# Power.net
KiCad netlist of a schematic drawn in Altium Designer
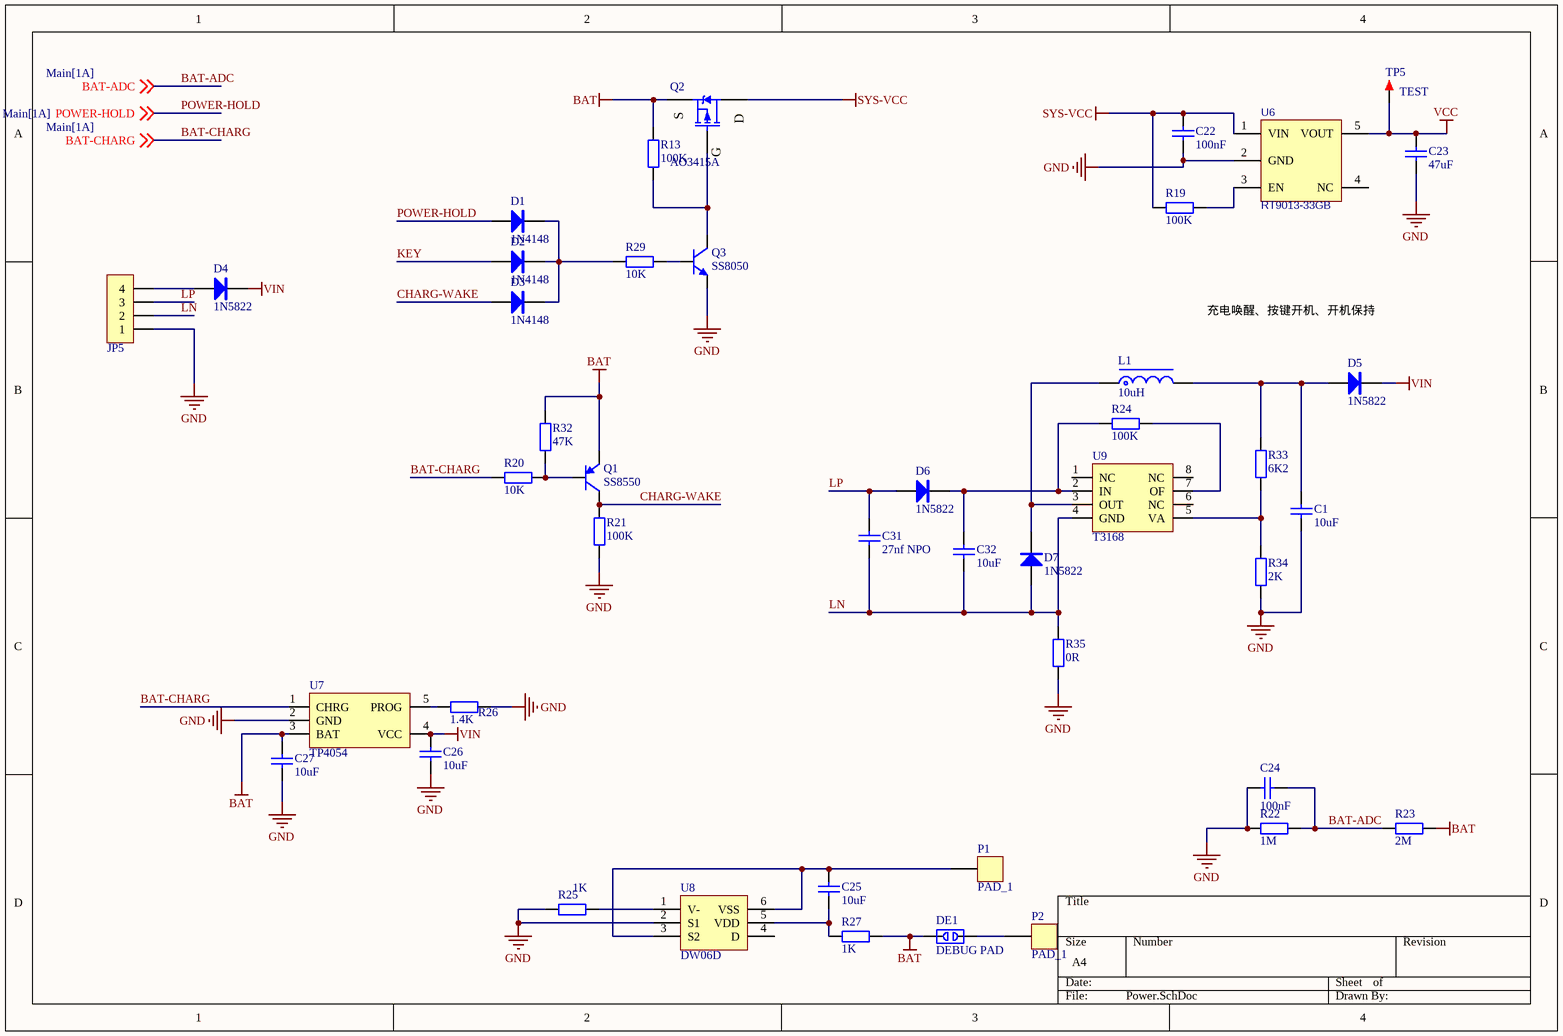
[diagram p0: Power.SchDoc]

(export (version "E")
  (design (tool "Eeschema 10.0.6"))
  (components
    (comp (ref "C1")
      (value "10uF")
      (footprint "C1206_M")
      (description "贴片电容/MLCC电容")
      (libsource (lib "0.1 - 电阻-电容-电感-晶振-晶体-磁珠-电位器-法拉电容-馈通电容") (part "C"))
    )
    (comp (ref "C22")
      (value "100nF")
      (footprint "C0402_M")
      (description "贴片电容/MLCC电容")
      (libsource (lib "0.1 - 电阻-电容-电感-晶振-晶体-磁珠-电位器-法拉电容-馈通电容") (part "C"))
    )
    (comp (ref "C23")
      (value "47uF")
      (footprint "C0603_L")
      (description "贴片电容/MLCC电容")
      (libsource (lib "0.1 - 电阻-电容-电感-晶振-晶体-磁珠-电位器-法拉电容-馈通电容") (part "C"))
    )
    (comp (ref "C24")
      (value "100nF")
      (footprint "C0402_M")
      (description "贴片电容/MLCC电容")
      (libsource (lib "0.1 - 电阻-电容-电感-晶振-晶体-磁珠-电位器-法拉电容-馈通电容") (part "C"))
    )
    (comp (ref "C25")
      (value "10uF")
      (footprint "C0402_M")
      (description "贴片电容/MLCC电容")
      (libsource (lib "0.1 - 电阻-电容-电感-晶振-晶体-磁珠-电位器-法拉电容-馈通电容") (part "C"))
    )
    (comp (ref "C26")
      (value "10uF")
      (footprint "C0402_M")
      (description "贴片电容/MLCC电容")
      (libsource (lib "0.1 - 电阻-电容-电感-晶振-晶体-磁珠-电位器-法拉电容-馈通电容") (part "C"))
    )
    (comp (ref "C27")
      (value "10uF")
      (footprint "C0402_M")
      (description "贴片电容/MLCC电容")
      (libsource (lib "0.1 - 电阻-电容-电感-晶振-晶体-磁珠-电位器-法拉电容-馈通电容") (part "C"))
    )
    (comp (ref "C31")
      (value "27nf NPO")
      (footprint "C1206_M")
      (description "贴片电容/MLCC电容")
      (libsource (lib "0.1 - 电阻-电容-电感-晶振-晶体-磁珠-电位器-法拉电容-馈通电容") (part "C"))
    )
    (comp (ref "C32")
      (value "10uF")
      (footprint "C1206_M")
      (description "贴片电容/MLCC电容")
      (libsource (lib "0.1 - 电阻-电容-电感-晶振-晶体-磁珠-电位器-法拉电容-馈通电容") (part "C"))
    )
    (comp (ref "D1")
      (value "1N4148")
      (footprint "SOD-323")
      (description "开关二极管")
      (libsource (lib "0.2 - 二极管-TVS-ESD-整流桥-放电管") (part "1N4148"))
    )
    (comp (ref "D2")
      (value "1N4148")
      (footprint "SOD-323")
      (description "开关二极管")
      (libsource (lib "0.2 - 二极管-TVS-ESD-整流桥-放电管") (part "1N4148"))
    )
    (comp (ref "D3")
      (value "1N4148")
      (footprint "SOD-323")
      (description "开关二极管")
      (libsource (lib "0.2 - 二极管-TVS-ESD-整流桥-放电管") (part "1N4148"))
    )
    (comp (ref "D4")
      (value "1N5822")
      (footprint "SOD-123")
      (description "肖特基二极管")
      (libsource (lib "0.2 - 二极管-TVS-ESD-整流桥-放电管") (part "1N5822"))
    )
    (comp (ref "D5")
      (value "1N5822")
      (footprint "SOD-123")
      (description "肖特基二极管")
      (libsource (lib "0.2 - 二极管-TVS-ESD-整流桥-放电管") (part "1N5822"))
    )
    (comp (ref "D6")
      (value "1N5822")
      (footprint "SOD-123")
      (description "肖特基二极管")
      (libsource (lib "0.2 - 二极管-TVS-ESD-整流桥-放电管") (part "1N5822"))
    )
    (comp (ref "D7")
      (value "1N5822")
      (footprint "SOD-123")
      (description "肖特基二极管")
      (libsource (lib "0.2 - 二极管-TVS-ESD-整流桥-放电管") (part "1N5822"))
    )
    (comp (ref "DE1")
      (value "DEBUG PAD")
      (footprint "DEBUG_A")
      (description "调试断点焊盘")
      (libsource (lib "0.5 - 按键_开关_蜂鸣器_保险丝_电池_测试点_Mark点_铜柱") (part "DEBUG"))
    )
    (comp (ref "JP5")
      (value "HDR-1X4")
      (footprint "HDR2.54-LI-4P")
      (description "4P接插件")
      (libsource (lib "5.5 - 2.54mm连接器(KF2EDGK_XH2.54_2.54排针排母)") (part "Header 4"))
    )
    (comp (ref "L1")
      (value "10uH")
      (footprint "SWPA3012")
      (description "顺络_SWPA贴片屏蔽电感")
      (libsource (lib "0.1 - 电阻-电容-电感-晶振-晶体-磁珠-电位器-法拉电容-馈通电容") (part "L-SWPA"))
    )
    (comp (ref "P1")
      (value "PAD_1")
      (footprint "PAD-3.2X1.7")
      (description "焊盘")
      (libsource (lib "0.5 - 按键_开关_蜂鸣器_保险丝_电池_测试点_Mark点_铜柱") (part "PAD_1"))
    )
    (comp (ref "P2")
      (value "PAD_1")
      (footprint "PAD-3.2X1.7")
      (description "焊盘")
      (libsource (lib "0.5 - 按键_开关_蜂鸣器_保险丝_电池_测试点_Mark点_铜柱") (part "PAD_1"))
    )
    (comp (ref "Q1")
      (value "SS8550")
      (footprint "SOT23-3N")
      (description "高频放大-PNP型")
      (libsource (lib "0.4 - 三极管-场效应管-可控硅") (part "8550-SMD"))
    )
    (comp (ref "Q2")
      (value "AO3415A")
      (footprint "SOT23-3N")
      (description "P沟道 20V/4A")
      (libsource (lib "0.4 - 三极管-场效应管-可控硅") (part "AO3415A"))
    )
    (comp (ref "Q3")
      (value "SS8050")
      (footprint "SOT23-3N")
      (description "高频放大-NPN型")
      (libsource (lib "0.4 - 三极管-场效应管-可控硅") (part "8050-SMD"))
    )
    (comp (ref "R13")
      (value "100K")
      (footprint "R0402_M")
      (description "贴片电阻")
      (libsource (lib "0.1 - 电阻-电容-电感-晶振-晶体-磁珠-电位器-法拉电容-馈通电容") (part "R"))
    )
    (comp (ref "R19")
      (value "100K")
      (footprint "R0402_M")
      (description "贴片电阻")
      (libsource (lib "0.1 - 电阻-电容-电感-晶振-晶体-磁珠-电位器-法拉电容-馈通电容") (part "R"))
    )
    (comp (ref "R20")
      (value "10K")
      (footprint "R0402_M")
      (description "贴片电阻")
      (libsource (lib "0.1 - 电阻-电容-电感-晶振-晶体-磁珠-电位器-法拉电容-馈通电容") (part "R"))
    )
    (comp (ref "R21")
      (value "100K")
      (footprint "R0402_M")
      (description "贴片电阻")
      (libsource (lib "0.1 - 电阻-电容-电感-晶振-晶体-磁珠-电位器-法拉电容-馈通电容") (part "R"))
    )
    (comp (ref "R22")
      (value "1M")
      (footprint "R0402_M")
      (description "贴片电阻")
      (libsource (lib "0.1 - 电阻-电容-电感-晶振-晶体-磁珠-电位器-法拉电容-馈通电容") (part "R"))
    )
    (comp (ref "R23")
      (value "2M")
      (footprint "R0402_M")
      (description "贴片电阻")
      (libsource (lib "0.1 - 电阻-电容-电感-晶振-晶体-磁珠-电位器-法拉电容-馈通电容") (part "R"))
    )
    (comp (ref "R24")
      (value "100K")
      (footprint "R0402_M")
      (description "贴片电阻")
      (libsource (lib "0.1 - 电阻-电容-电感-晶振-晶体-磁珠-电位器-法拉电容-馈通电容") (part "R"))
    )
    (comp (ref "R25")
      (value "1K")
      (footprint "R0402_M")
      (description "贴片电阻")
      (libsource (lib "0.1 - 电阻-电容-电感-晶振-晶体-磁珠-电位器-法拉电容-馈通电容") (part "R"))
    )
    (comp (ref "R26")
      (value "1.4K")
      (footprint "R0402_M")
      (description "贴片电阻")
      (libsource (lib "0.1 - 电阻-电容-电感-晶振-晶体-磁珠-电位器-法拉电容-馈通电容") (part "R"))
    )
    (comp (ref "R27")
      (value "1K")
      (footprint "R0402_M")
      (description "贴片电阻")
      (libsource (lib "0.1 - 电阻-电容-电感-晶振-晶体-磁珠-电位器-法拉电容-馈通电容") (part "R"))
    )
    (comp (ref "R29")
      (value "10K")
      (footprint "R0402_M")
      (description "贴片电阻")
      (libsource (lib "0.1 - 电阻-电容-电感-晶振-晶体-磁珠-电位器-法拉电容-馈通电容") (part "R"))
    )
    (comp (ref "R32")
      (value "47K")
      (footprint "R0402_M")
      (description "贴片电阻")
      (libsource (lib "0.1 - 电阻-电容-电感-晶振-晶体-磁珠-电位器-法拉电容-馈通电容") (part "R"))
    )
    (comp (ref "R33")
      (value "6K2")
      (footprint "R0402_M")
      (description "贴片电阻")
      (libsource (lib "0.1 - 电阻-电容-电感-晶振-晶体-磁珠-电位器-法拉电容-馈通电容") (part "R"))
    )
    (comp (ref "R34")
      (value "2K")
      (footprint "R0402_M")
      (description "贴片电阻")
      (libsource (lib "0.1 - 电阻-电容-电感-晶振-晶体-磁珠-电位器-法拉电容-馈通电容") (part "R"))
    )
    (comp (ref "R35")
      (value "0R")
      (footprint "R0805_M")
      (description "贴片电阻")
      (libsource (lib "0.1 - 电阻-电容-电感-晶振-晶体-磁珠-电位器-法拉电容-馈通电容") (part "R"))
    )
    (comp (ref "TP5")
      (value "TEST")
      (footprint "TEST 1.2")
      (description "测试点")
      (libsource (lib "0.5 - 按键_开关_蜂鸣器_保险丝_电池_测试点_Mark点_铜柱") (part "TEST"))
    )
    (comp (ref "U6")
      (value "RT9013-33GB")
      (footprint "SOT-23-5")
      (description "LDO 3.3V/0.5A")
      (libsource (lib "0.7 - 电源类芯片") (part "RT9013-33GB"))
    )
    (comp (ref "U7")
      (value "TP4054")
      (footprint "SOT23-5")
      (description "锂电池充电芯片")
      (libsource (lib "0.7 - 电源类芯片") (part "TP4054"))
    )
    (comp (ref "U8")
      (value "DW06D")
      (footprint "SOT23-6L")
      (description "二合一锂电池保护IC")
      (libsource (lib "0.8 - 常见芯片") (part "DW06D"))
    )
    (comp (ref "U9")
      (value "T3168")
      (footprint "SOP8")
      (description "T3168无线充芯片")
      (libsource (lib "0.7 - 电源类芯片") (part "T3168"))
    )
  )
  (nets
    (net (code "1") (name "/CHARG-WAKE") (class "Default")
      (node (ref "D3") (pin "1") (pinfunction "A_1") (pintype "passive"))
      (node (ref "Q1") (pin "3") (pinfunction "C_3") (pintype "passive"))
      (node (ref "R21") (pin "2") (pinfunction "2_2") (pintype "passive"))
    )
    (net (code "2") (name "/KEY") (class "Default")
      (node (ref "D2") (pin "1") (pinfunction "A_1") (pintype "passive"))
    )
    (net (code "3") (name "/LN") (class "Default")
      (node (ref "C31") (pin "1") (pinfunction "1_1") (pintype "passive"))
      (node (ref "C32") (pin "1") (pinfunction "1_1") (pintype "passive"))
      (node (ref "D7") (pin "1") (pinfunction "A_1") (pintype "passive"))
      (node (ref "JP5") (pin "2") (pinfunction "2_2") (pintype "passive"))
      (node (ref "R35") (pin "1") (pinfunction "1_1") (pintype "passive"))
      (node (ref "U9") (pin "4") (pinfunction "GND_4") (pintype "passive"))
    )
    (net (code "4") (name "/LP") (class "Default")
      (node (ref "C31") (pin "2") (pinfunction "2_2") (pintype "passive"))
      (node (ref "D6") (pin "1") (pinfunction "A_1") (pintype "passive"))
      (node (ref "JP5") (pin "3") (pinfunction "3_3") (pintype "passive"))
    )
    (net (code "5") (name "BAT") (class "Default")
      (node (ref "C27") (pin "1") (pinfunction "1_1") (pintype "passive"))
      (node (ref "DE1") (pin "1") (pinfunction "1_1") (pintype "passive"))
      (node (ref "Q1") (pin "2") (pinfunction "E_2") (pintype "passive"))
      (node (ref "Q2") (pin "2") (pinfunction "S_2") (pintype "passive"))
      (node (ref "R13") (pin "2") (pinfunction "2_2") (pintype "passive"))
      (node (ref "R23") (pin "2") (pinfunction "2_2") (pintype "passive"))
      (node (ref "R27") (pin "2") (pinfunction "2_2") (pintype "passive"))
      (node (ref "R32") (pin "2") (pinfunction "2_2") (pintype "passive"))
      (node (ref "U7") (pin "3") (pinfunction "BAT_3") (pintype "passive"))
    )
    (net (code "6") (name "BAT-ADC") (class "Default")
      (node (ref "C24") (pin "1") (pinfunction "1_1") (pintype "passive"))
      (node (ref "R22") (pin "2") (pinfunction "2_2") (pintype "passive"))
      (node (ref "R23") (pin "1") (pinfunction "1_1") (pintype "passive"))
    )
    (net (code "7") (name "BAT-CHARG") (class "Default")
      (node (ref "R20") (pin "2") (pinfunction "2_2") (pintype "passive"))
      (node (ref "U7") (pin "1") (pinfunction "CHRG_1") (pintype "passive"))
    )
    (net (code "8") (name "GND") (class "Default")
      (node (ref "C1") (pin "1") (pinfunction "1_1") (pintype "passive"))
      (node (ref "C22") (pin "1") (pinfunction "1_1") (pintype "passive"))
      (node (ref "C23") (pin "1") (pinfunction "1_1") (pintype "passive"))
      (node (ref "C24") (pin "2") (pinfunction "2_2") (pintype "passive"))
      (node (ref "C26") (pin "2") (pinfunction "2_2") (pintype "passive"))
      (node (ref "C27") (pin "2") (pinfunction "2_2") (pintype "passive"))
      (node (ref "JP5") (pin "1") (pinfunction "1_1") (pintype "passive"))
      (node (ref "Q3") (pin "2") (pinfunction "E_2") (pintype "passive"))
      (node (ref "R21") (pin "1") (pinfunction "1_1") (pintype "passive"))
      (node (ref "R22") (pin "1") (pinfunction "1_1") (pintype "passive"))
      (node (ref "R25") (pin "1") (pinfunction "1_1") (pintype "passive"))
      (node (ref "R26") (pin "2") (pinfunction "2_2") (pintype "passive"))
      (node (ref "R34") (pin "1") (pinfunction "1_1") (pintype "passive"))
      (node (ref "R35") (pin "2") (pinfunction "2_2") (pintype "passive"))
      (node (ref "U6") (pin "2") (pinfunction "GND_2") (pintype "passive"))
      (node (ref "U7") (pin "2") (pinfunction "GND_2") (pintype "passive"))
      (node (ref "U8") (pin "2") (pinfunction "S1_2") (pintype "passive"))
    )
    (net (code "9") (name "Net-(D1-K)") (class "Default")
      (node (ref "D1") (pin "2") (pinfunction "K_2") (pintype "passive"))
      (node (ref "D2") (pin "2") (pinfunction "K_2") (pintype "passive"))
      (node (ref "D3") (pin "2") (pinfunction "K_2") (pintype "passive"))
      (node (ref "R29") (pin "2") (pinfunction "2_2") (pintype "passive"))
    )
    (net (code "10") (name "Net-(D4-A)") (class "Default")
      (node (ref "D4") (pin "1") (pinfunction "A_1") (pintype "passive"))
      (node (ref "JP5") (pin "4") (pinfunction "4_4") (pintype "passive"))
    )
    (net (code "11") (name "Net-(D5-A)") (class "Default")
      (node (ref "C1") (pin "2") (pinfunction "2_2") (pintype "passive"))
      (node (ref "D5") (pin "1") (pinfunction "A_1") (pintype "passive"))
      (node (ref "L1") (pin "2") (pinfunction "2_2") (pintype "passive"))
      (node (ref "R33") (pin "2") (pinfunction "2_2") (pintype "passive"))
    )
    (net (code "12") (name "Net-(D6-K)") (class "Default")
      (node (ref "C32") (pin "2") (pinfunction "2_2") (pintype "passive"))
      (node (ref "D6") (pin "2") (pinfunction "K_2") (pintype "passive"))
      (node (ref "R24") (pin "1") (pinfunction "1_1") (pintype "passive"))
      (node (ref "U9") (pin "2") (pinfunction "IN_2") (pintype "passive"))
    )
    (net (code "13") (name "Net-(D7-K)") (class "Default")
      (node (ref "D7") (pin "2") (pinfunction "K_2") (pintype "passive"))
      (node (ref "L1") (pin "1") (pinfunction "1_1") (pintype "passive"))
      (node (ref "U9") (pin "3") (pinfunction "OUT_3") (pintype "passive"))
    )
    (net (code "14") (name "Net-(DE1-Pad2)") (class "Default")
      (node (ref "DE1") (pin "2") (pinfunction "2_2") (pintype "passive"))
      (node (ref "P2") (pin "1") (pinfunction "1_1") (pintype "passive"))
    )
    (net (code "15") (name "Net-(Q1-B)") (class "Default")
      (node (ref "Q1") (pin "1") (pinfunction "B_1") (pintype "passive"))
      (node (ref "R20") (pin "1") (pinfunction "1_1") (pintype "passive"))
      (node (ref "R32") (pin "1") (pinfunction "1_1") (pintype "passive"))
    )
    (net (code "16") (name "Net-(Q2-G)") (class "Default")
      (node (ref "Q2") (pin "1") (pinfunction "G_1") (pintype "passive"))
      (node (ref "Q3") (pin "3") (pinfunction "C_3") (pintype "passive"))
      (node (ref "R13") (pin "1") (pinfunction "1_1") (pintype "passive"))
    )
    (net (code "17") (name "Net-(Q3-B)") (class "Default")
      (node (ref "Q3") (pin "1") (pinfunction "B_1") (pintype "passive"))
      (node (ref "R29") (pin "1") (pinfunction "1_1") (pintype "passive"))
    )
    (net (code "18") (name "Net-(U6-EN)") (class "Default")
      (node (ref "R19") (pin "2") (pinfunction "2_2") (pintype "passive"))
      (node (ref "U6") (pin "3") (pinfunction "EN_3") (pintype "passive"))
    )
    (net (code "19") (name "Net-(U7-PROG)") (class "Default")
      (node (ref "R26") (pin "1") (pinfunction "1_1") (pintype "passive"))
      (node (ref "U7") (pin "5") (pinfunction "PROG_5") (pintype "passive"))
    )
    (net (code "20") (name "Net-(U8-S2)") (class "Default")
      (node (ref "C25") (pin "1") (pinfunction "1_1") (pintype "passive"))
      (node (ref "P1") (pin "1") (pinfunction "1_1") (pintype "passive"))
      (node (ref "U8") (pin "3") (pinfunction "S2_3") (pintype "passive"))
      (node (ref "U8") (pin "6") (pinfunction "VSS_6") (pintype "passive"))
    )
    (net (code "21") (name "Net-(U8-V-)") (class "Default")
      (node (ref "R25") (pin "2") (pinfunction "2_2") (pintype "passive"))
      (node (ref "U8") (pin "1") (pinfunction "V-_1") (pintype "passive"))
    )
    (net (code "22") (name "Net-(U8-VDD)") (class "Default")
      (node (ref "C25") (pin "2") (pinfunction "2_2") (pintype "passive"))
      (node (ref "R27") (pin "1") (pinfunction "1_1") (pintype "passive"))
      (node (ref "U8") (pin "5") (pinfunction "VDD_5") (pintype "passive"))
    )
    (net (code "23") (name "Net-(U9-OF)") (class "Default")
      (node (ref "R24") (pin "2") (pinfunction "2_2") (pintype "passive"))
      (node (ref "U9") (pin "7") (pinfunction "OF_7") (pintype "passive"))
    )
    (net (code "24") (name "Net-(U9-VA)") (class "Default")
      (node (ref "R33") (pin "1") (pinfunction "1_1") (pintype "passive"))
      (node (ref "R34") (pin "2") (pinfunction "2_2") (pintype "passive"))
      (node (ref "U9") (pin "5") (pinfunction "VA_5") (pintype "passive"))
    )
    (net (code "25") (name "POWER-HOLD") (class "Default")
      (node (ref "D1") (pin "1") (pinfunction "A_1") (pintype "passive"))
    )
    (net (code "26") (name "SYS-VCC") (class "Default")
      (node (ref "C22") (pin "2") (pinfunction "2_2") (pintype "passive"))
      (node (ref "Q2") (pin "3") (pinfunction "D_3") (pintype "passive"))
      (node (ref "R19") (pin "1") (pinfunction "1_1") (pintype "passive"))
      (node (ref "U6") (pin "1") (pinfunction "VIN_1") (pintype "passive"))
    )
    (net (code "27") (name "VCC") (class "Default")
      (node (ref "C23") (pin "2") (pinfunction "2_2") (pintype "passive"))
      (node (ref "TP5") (pin "1") (pinfunction "1_1") (pintype "passive"))
      (node (ref "U6") (pin "5") (pinfunction "VOUT_5") (pintype "passive"))
    )
    (net (code "28") (name "VIN") (class "Default")
      (node (ref "C26") (pin "1") (pinfunction "1_1") (pintype "passive"))
      (node (ref "D4") (pin "2") (pinfunction "K_2") (pintype "passive"))
      (node (ref "D5") (pin "2") (pinfunction "K_2") (pintype "passive"))
      (node (ref "U7") (pin "4") (pinfunction "VCC_4") (pintype "passive"))
    )
    (net (code "29") (name "unconnected-(U6-NC-Pad4)") (class "Default")
      (node (ref "U6") (pin "4") (pinfunction "NC_4") (pintype "passive"))
    )
    (net (code "30") (name "unconnected-(U8-D-Pad4)") (class "Default")
      (node (ref "U8") (pin "4") (pinfunction "D_4") (pintype "passive"))
    )
    (net (code "31") (name "unconnected-(U9-NC-Pad1)") (class "Default")
      (node (ref "U9") (pin "1") (pinfunction "NC_1") (pintype "passive"))
    )
    (net (code "32") (name "unconnected-(U9-NC-Pad6)") (class "Default")
      (node (ref "U9") (pin "6") (pinfunction "NC_6") (pintype "passive"))
    )
    (net (code "33") (name "unconnected-(U9-NC-Pad8)") (class "Default")
      (node (ref "U9") (pin "8") (pinfunction "NC_8") (pintype "passive"))
    )
  )
)
